# wireless-ac-motor-controller-mk-1_0.net
KiCad netlist of a schematic drawn in EAGLE
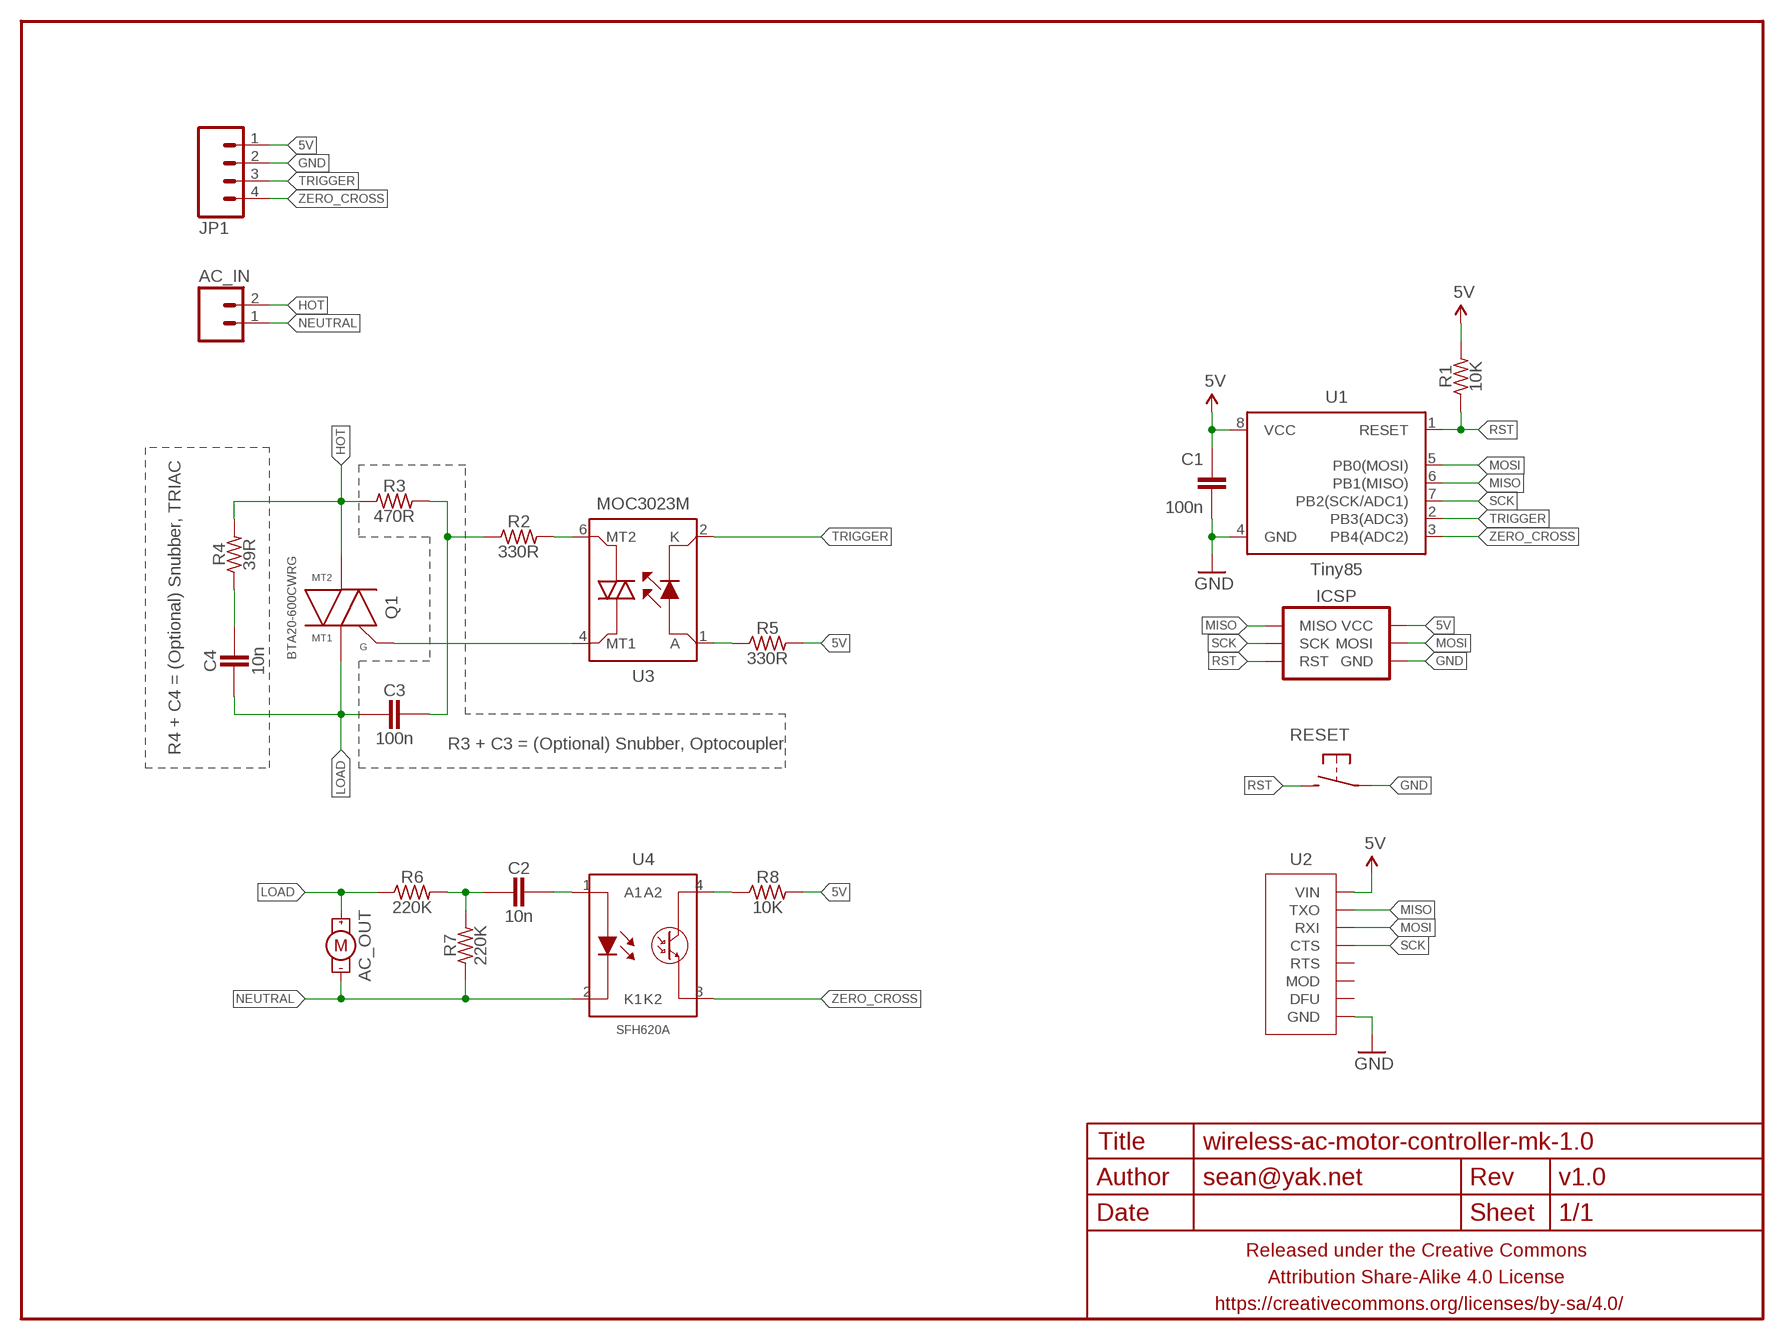
[diagram p0: schematic, sheet 1]

(export (version "E")
  (design (tool "Eeschema 10.0.6"))
  (components
    (comp (ref "AC_IN")
      (value "SCREWTERMINAL-25MM")
      (footprint "eagle-import:SCREWTERM-5MM-2")
      (libsource (lib "eagle-import") (part "SCREWTERMINAL-25MM"))
    )
    (comp (ref "AC_OUT")
      (value "MOTOR5MM-SCREW-TERM")
      (footprint "eagle-import:1X02_5MM_SCREW")
      (libsource (lib "eagle-import") (part "MOTOR5MM-SCREW-TERM"))
    )
    (comp (ref "C1")
      (value "100n")
      (footprint "eagle-import:C0805")
      (libsource (lib "eagle-import") (part "CAPACITOR-CERAMICC0805"))
    )
    (comp (ref "C2")
      (value "10n")
      (footprint "eagle-import:C0805")
      (libsource (lib "eagle-import") (part "CAPACITOR-CERAMICC0805"))
    )
    (comp (ref "C3")
      (value "100n")
      (footprint "eagle-import:C025-024X044")
      (libsource (lib "eagle-import") (part "CAPACITOR-CERAMIC025-024X044"))
    )
    (comp (ref "C4")
      (value "10n")
      (footprint "eagle-import:C025-024X044")
      (libsource (lib "eagle-import") (part "CAPACITOR-CERAMIC025-024X044"))
    )
    (comp (ref "FRAME1")
      (value "FRAME-LETTERNO_PACKAGE")
      (footprint "eagle-import:DUMMY")
      (fields (field (name "DESIGNER") "sean@yak.net") (field (name "VERSION") "v1.0"))
      (libsource (lib "eagle-import") (part "FRAME-LETTERNO_PACKAGE"))
    )
    (comp (ref "ICSP")
      (value "AVR_SPI_PRG_6PTH")
      (footprint "eagle-import:2X3")
      (libsource (lib "eagle-import") (part "AVR_SPI_PRG_6PTH"))
    )
    (comp (ref "JP1")
      (value "M04JST-PTH-VERT")
      (footprint "eagle-import:JST-4-PH-VERT-PTH")
      (libsource (lib "eagle-import") (part "M04JST-PTH-VERT"))
    )
    (comp (ref "Q1")
      (value "BTA20-600CWRG")
      (footprint "eagle-import:TO220V")
      (libsource (lib "eagle-import") (part "TRIACTO-220-VERT"))
    )
    (comp (ref "R1")
      (value "10K")
      (footprint "eagle-import:R0805")
      (libsource (lib "eagle-import") (part "RESISTORR0805"))
    )
    (comp (ref "R2")
      (value "330R")
      (footprint "eagle-import:RESISTOR-AXIAL-PTH-5.08MM")
      (libsource (lib "eagle-import") (part "RESISTORPTH-AXIAL-5.08MM"))
    )
    (comp (ref "R3")
      (value "470R")
      (footprint "eagle-import:RESISTOR-AXIAL-PTH-7.62MM")
      (libsource (lib "eagle-import") (part "RESISTORPTH-AXIAL-7.62MM"))
    )
    (comp (ref "R4")
      (value "39R")
      (footprint "eagle-import:RESISTOR-AXIAL-PTH-7.62MM")
      (libsource (lib "eagle-import") (part "RESISTORPTH-AXIAL-7.62MM"))
    )
    (comp (ref "R5")
      (value "330R")
      (footprint "eagle-import:R0805")
      (libsource (lib "eagle-import") (part "RESISTORR0805"))
    )
    (comp (ref "R6")
      (value "220K")
      (footprint "eagle-import:RESISTOR-AXIAL-PTH-6.35MM")
      (libsource (lib "eagle-import") (part "RESISTORPTH-AXIAL-6.35MM"))
    )
    (comp (ref "R7")
      (value "220K")
      (footprint "eagle-import:RESISTOR-AXIAL-PTH-6.35MM")
      (libsource (lib "eagle-import") (part "RESISTORPTH-AXIAL-6.35MM"))
    )
    (comp (ref "R8")
      (value "10K")
      (footprint "eagle-import:RESISTOR-AXIAL-PTH-7.62MM")
      (libsource (lib "eagle-import") (part "RESISTORPTH-AXIAL-7.62MM"))
    )
    (comp (ref "RESET")
      (value "SPST-NO-TACT3MM-PTH-SMALL-PADS")
      (footprint "eagle-import:DTS-3-SMALL-PADS")
      (libsource (lib "eagle-import") (part "SPST-NO-TACT3MM-PTH-SMALL-PADS"))
    )
    (comp (ref "U1")
      (value "Tiny85")
      (footprint "eagle-import:SO08-EIAJ")
      (libsource (lib "eagle-import") (part "ATTINY45TINY85-20-SOICW"))
    )
    (comp (ref "U2")
      (value "ADAFRUIT_BLE_UARTBARE")
      (footprint "eagle-import:ADAFRUIT_BLE_UART")
      (libsource (lib "eagle-import") (part "ADAFRUIT_BLE_UARTBARE"))
    )
    (comp (ref "U3")
      (value "MOC3023M")
      (footprint "eagle-import:DIP06")
      (libsource (lib "eagle-import") (part "MOC30XXMOC30XXM-DIP6"))
    )
    (comp (ref "U4")
      (value "SFH620A")
      (footprint "eagle-import:DIL04")
      (libsource (lib "eagle-import") (part "OPTOISOLATORDIP4"))
    )
  )
  (nets
    (net (code "1") (name "5V") (class "Default")
      (node (ref "C1") (pin "1") (pinfunction "1_1") (pintype "passive"))
      (node (ref "ICSP") (pin "2") (pinfunction "VCC_2") (pintype "passive"))
      (node (ref "JP1") (pin "1") (pinfunction "1_1") (pintype "passive"))
      (node (ref "R1") (pin "2") (pinfunction "2_2") (pintype "passive"))
      (node (ref "R5") (pin "2") (pinfunction "2_2") (pintype "passive"))
      (node (ref "R8") (pin "P$2") (pinfunction "2_P$2") (pintype "passive"))
      (node (ref "U1") (pin "8") (pinfunction "VCC_8") (pintype "bidirectional"))
      (node (ref "U2") (pin "VIN") (pinfunction "VIN_VIN") (pintype "bidirectional"))
    )
    (net (code "2") (name "GND") (class "Default")
      (node (ref "C1") (pin "2") (pinfunction "2_2") (pintype "passive"))
      (node (ref "ICSP") (pin "6") (pinfunction "GND_6") (pintype "passive"))
      (node (ref "JP1") (pin "2") (pinfunction "2_2") (pintype "passive"))
      (node (ref "RESET") (pin "1") (pinfunction "1_1") (pintype "passive"))
      (node (ref "U1") (pin "4") (pinfunction "GND_4") (pintype "bidirectional"))
      (node (ref "U2") (pin "GND") (pinfunction "GND_GND") (pintype "bidirectional"))
    )
    (net (code "3") (name "HOT") (class "Default")
      (node (ref "AC_IN") (pin "2") (pinfunction "2_2") (pintype "passive"))
      (node (ref "Q1") (pin "2") (pinfunction "MT2_2") (pintype "bidirectional"))
      (node (ref "R3") (pin "P$1") (pinfunction "1_P$1") (pintype "passive"))
      (node (ref "R4") (pin "P$2") (pinfunction "2_P$2") (pintype "passive"))
    )
    (net (code "4") (name "LOAD") (class "Default")
      (node (ref "AC_OUT") (pin "1") (pinfunction "+_1") (pintype "bidirectional"))
      (node (ref "C3") (pin "2") (pinfunction "2_2") (pintype "passive"))
      (node (ref "C4") (pin "2") (pinfunction "2_2") (pintype "passive"))
      (node (ref "Q1") (pin "1") (pinfunction "MT1_1") (pintype "bidirectional"))
      (node (ref "R6") (pin "P$1") (pinfunction "1_P$1") (pintype "passive"))
    )
    (net (code "5") (name "MISO") (class "Default")
      (node (ref "ICSP") (pin "1") (pinfunction "MISO_1") (pintype "passive"))
      (node (ref "U1") (pin "6") (pinfunction "PB1(MISO)_6") (pintype "bidirectional"))
      (node (ref "U2") (pin "TXO") (pinfunction "TXO_TXO") (pintype "bidirectional"))
    )
    (net (code "6") (name "MOSI") (class "Default")
      (node (ref "ICSP") (pin "4") (pinfunction "MOSI_4") (pintype "passive"))
      (node (ref "U1") (pin "5") (pinfunction "PB0(MOSI)_5") (pintype "bidirectional"))
      (node (ref "U2") (pin "RXI") (pinfunction "RXI_RXI") (pintype "bidirectional"))
    )
    (net (code "7") (name "NEUTRAL") (class "Default")
      (node (ref "AC_IN") (pin "1") (pinfunction "1_1") (pintype "passive"))
      (node (ref "AC_OUT") (pin "2") (pinfunction "-_2") (pintype "bidirectional"))
      (node (ref "R7") (pin "P$1") (pinfunction "1_P$1") (pintype "passive"))
      (node (ref "U4") (pin "2") (pinfunction "K1_2") (pintype "bidirectional"))
    )
    (net (code "8") (name "Net-(Q1-GATE)") (class "Default")
      (node (ref "Q1") (pin "3") (pinfunction "GATE_3") (pintype "bidirectional"))
      (node (ref "U3") (pin "4") (pinfunction "MT1_4") (pintype "bidirectional"))
    )
    (net (code "9") (name "Net-(R2-1)") (class "Default")
      (node (ref "C3") (pin "1") (pinfunction "1_1") (pintype "passive"))
      (node (ref "R2") (pin "P$1") (pinfunction "1_P$1") (pintype "passive"))
      (node (ref "R3") (pin "P$2") (pinfunction "2_P$2") (pintype "passive"))
    )
    (net (code "10") (name "Net-(R2-2)") (class "Default")
      (node (ref "R2") (pin "P$2") (pinfunction "2_P$2") (pintype "passive"))
      (node (ref "U3") (pin "6") (pinfunction "MT2_6") (pintype "bidirectional"))
    )
    (net (code "11") (name "Net-(R4-1)") (class "Default")
      (node (ref "C4") (pin "1") (pinfunction "1_1") (pintype "passive"))
      (node (ref "R4") (pin "P$1") (pinfunction "1_P$1") (pintype "passive"))
    )
    (net (code "12") (name "Net-(R6-2)") (class "Default")
      (node (ref "C2") (pin "2") (pinfunction "2_2") (pintype "passive"))
      (node (ref "R6") (pin "P$2") (pinfunction "2_P$2") (pintype "passive"))
      (node (ref "R7") (pin "P$2") (pinfunction "2_P$2") (pintype "passive"))
    )
    (net (code "13") (name "Net-(R8-1)") (class "Default")
      (node (ref "R8") (pin "P$1") (pinfunction "1_P$1") (pintype "passive"))
      (node (ref "U4") (pin "4") (pinfunction "A2_4") (pintype "bidirectional"))
    )
    (net (code "14") (name "Net-(U3-A)") (class "Default")
      (node (ref "R5") (pin "1") (pinfunction "1_1") (pintype "passive"))
      (node (ref "U3") (pin "1") (pinfunction "A_1") (pintype "bidirectional"))
    )
    (net (code "15") (name "Net-(U4-A1)") (class "Default")
      (node (ref "C2") (pin "1") (pinfunction "1_1") (pintype "passive"))
      (node (ref "U4") (pin "1") (pinfunction "A1_1") (pintype "bidirectional"))
    )
    (net (code "16") (name "RST") (class "Default")
      (node (ref "ICSP") (pin "5") (pinfunction "RST_5") (pintype "passive"))
      (node (ref "R1") (pin "1") (pinfunction "1_1") (pintype "passive"))
      (node (ref "RESET") (pin "2") (pinfunction "2_2") (pintype "passive"))
      (node (ref "U1") (pin "1") (pinfunction "RESET_1") (pintype "bidirectional"))
    )
    (net (code "17") (name "SCK") (class "Default")
      (node (ref "ICSP") (pin "3") (pinfunction "SCK_3") (pintype "passive"))
      (node (ref "U1") (pin "7") (pinfunction "PB2(SCK/ADC1)_7") (pintype "bidirectional"))
      (node (ref "U2") (pin "CTS") (pinfunction "CTS_CTS") (pintype "bidirectional"))
    )
    (net (code "18") (name "TRIGGER") (class "Default")
      (node (ref "JP1") (pin "3") (pinfunction "3_3") (pintype "passive"))
      (node (ref "U1") (pin "2") (pinfunction "PB3(ADC3)_2") (pintype "bidirectional"))
      (node (ref "U3") (pin "2") (pinfunction "K_2") (pintype "bidirectional"))
    )
    (net (code "19") (name "ZERO_CROSS") (class "Default")
      (node (ref "JP1") (pin "4") (pinfunction "4_4") (pintype "passive"))
      (node (ref "U1") (pin "3") (pinfunction "PB4(ADC2)_3") (pintype "bidirectional"))
      (node (ref "U4") (pin "3") (pinfunction "K2_3") (pintype "bidirectional"))
    )
    (net (code "20") (name "unconnected-(U2-PadDFU)") (class "Default")
      (node (ref "U2") (pin "DFU") (pinfunction "DFU_DFU") (pintype "bidirectional"))
    )
    (net (code "21") (name "unconnected-(U2-PadMOD)") (class "Default")
      (node (ref "U2") (pin "MOD") (pinfunction "MOD_MOD") (pintype "bidirectional"))
    )
    (net (code "22") (name "unconnected-(U2-PadRTS)") (class "Default")
      (node (ref "U2") (pin "RTS") (pinfunction "RTS_RTS") (pintype "bidirectional"))
    )
  )
)
